# MMC5983MA.net
KiCad netlist of a schematic drawn in Altium Designer
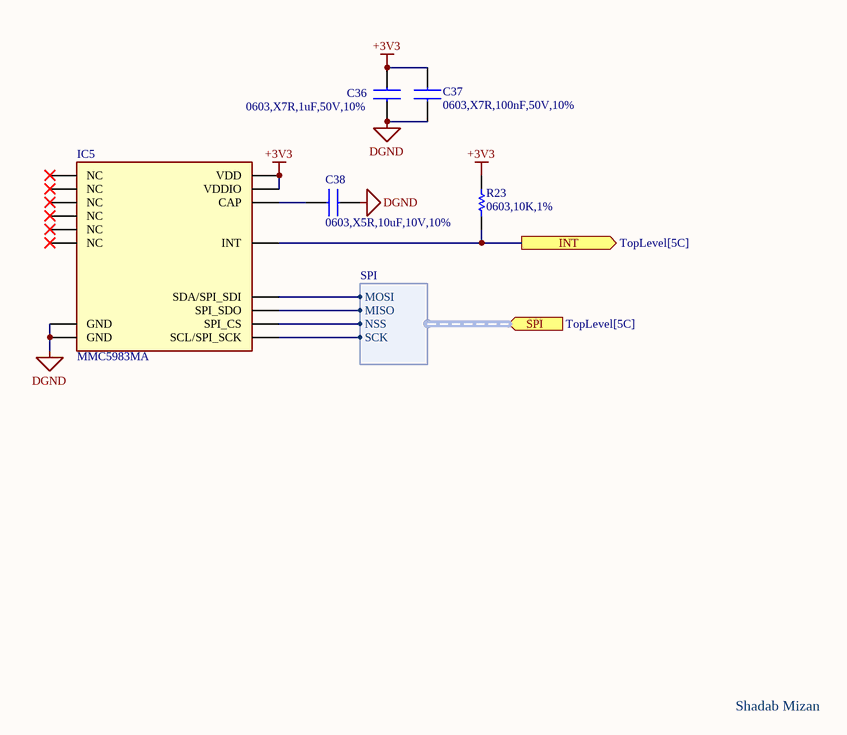
[diagram p0: MMC5983MA.SchDoc]

(export (version "E")
  (design (tool "Eeschema 10.0.6"))
  (components
    (comp (ref "C36")
      (value "0603,X7R,1uF,50V,10%")
      (footprint "CAPC1608X90N")
      (description "50V 1uF X7R ±10% 0603 Multilayer Ceramic Capacitors MLCC - SMD/SMT ROHS")
      (fields (field (name "LCSC PART #") "C15849") (field (name "MANU PART #") "CL10A105KB8NNNC"))
      (libsource (lib "flight-controller") (part "CL10A105KB8NNNC"))
    )
    (comp (ref "C37")
      (value "0603,X7R,100nF,50V,10%")
      (footprint "CAPC1608X90N")
      (description "50V 100nF X7R ±10% 0603 Multilayer Ceramic Capacitors MLCC - SMD/SMT ROHS")
      (fields (field (name "LCSC PART #") "C14663") (field (name "MANU PART #") "CC0603KRX7R9BB104"))
      (libsource (lib "flight-controller") (part "CC0603KRX7R9BB104"))
    )
    (comp (ref "C38")
      (value "0603,X5R,10uF,10V,10%")
      (footprint "CAPC1608X90N")
      (description "10uF ±10% 10V Ceramic Capacitor X5R 0603")
      (fields (field (name "LCSC PART #") "C19702") (field (name "MANU PART #") "CL10A106KP8NNNC"))
      (libsource (lib "flight-controller") (part "CL10A106KP8NNNC"))
    )
    (comp (ref "IC5")
      (value "MMC5983MA")
      (footprint "LGA-16_L3.0-W3.0-P0.50-BL_SQ")
      (description "±8 Gauss, High Performance 3-axis Magnetic Sensor")
      (fields (field (name "LCSC PART #") "C404329"))
      (libsource (lib "flight-controller") (part "MMC5983MA"))
    )
    (comp (ref "R23")
      (value "0603,10K,1%")
      (footprint "RESC1608X90N")
      (description "100mW Thick Film Resistor 75V ±100ppm/℃ ±1% 10kΩ 0603 Chip Resistor - Surface Mount ROHS")
      (fields (field (name "LCSC PART #") "C25804") (field (name "MANU PART #") "0603WAF1002T5E"))
      (libsource (lib "flight-controller") (part "0603WAF1002T5E"))
    )
  )
  (nets
    (net (code "2") (name "+3V3") (class "Default")
      (node (ref "C36") (pin "2") (pinfunction "2_2") (pintype "passive"))
      (node (ref "C37") (pin "2") (pinfunction "2_2") (pintype "passive"))
      (node (ref "IC5") (pin "13") (pinfunction "VDDIO_13") (pintype "passive"))
      (node (ref "IC5") (pin "2") (pinfunction "VDD_2") (pintype "passive"))
      (node (ref "R23") (pin "2") (pinfunction "2_2") (pintype "passive"))
    )
    (net (code "3") (name "/INT") (class "Default")
      (node (ref "IC5") (pin "15") (pinfunction "INT_15") (pintype "passive"))
      (node (ref "R23") (pin "1") (pinfunction "1_1") (pintype "passive"))
    )
    (net (code "4") (name "/MISO") (class "Default")
      (node (ref "IC5") (pin "5") (pinfunction "SPI_SDO_5") (pintype "passive"))
    )
    (net (code "5") (name "/MOSI") (class "Default")
      (node (ref "IC5") (pin "16") (pinfunction "SDA/SPI_SDI_16") (pintype "passive"))
    )
    (net (code "6") (name "/NSS") (class "Default")
      (node (ref "IC5") (pin "4") (pinfunction "SPI_CS_4") (pintype "passive"))
    )
    (net (code "7") (name "/SCK") (class "Default")
      (node (ref "IC5") (pin "1") (pinfunction "SCL/SPI_SCK_1") (pintype "passive"))
    )
    (net (code "9") (name "DGND") (class "Default")
      (node (ref "C36") (pin "1") (pinfunction "1_1") (pintype "passive"))
      (node (ref "C37") (pin "1") (pinfunction "1_1") (pintype "passive"))
      (node (ref "C38") (pin "2") (pinfunction "2_2") (pintype "passive"))
      (node (ref "IC5") (pin "11") (pinfunction "GND_11") (pintype "passive"))
      (node (ref "IC5") (pin "9") (pinfunction "GND_9") (pintype "passive"))
    )
    (net (code "10") (name "Net-(IC5-CAP)") (class "Default")
      (node (ref "C38") (pin "1") (pinfunction "1_1") (pintype "passive"))
      (node (ref "IC5") (pin "10") (pinfunction "CAP_10") (pintype "passive"))
    )
    (net (code "11") (name "unconnected-(IC5-NC-Pad3)") (class "Default")
      (node (ref "IC5") (pin "3") (pinfunction "NC_3") (pintype "passive+no_connect"))
    )
    (net (code "12") (name "unconnected-(IC5-NC-Pad6)") (class "Default")
      (node (ref "IC5") (pin "6") (pinfunction "NC_6") (pintype "passive+no_connect"))
    )
    (net (code "13") (name "unconnected-(IC5-NC-Pad7)") (class "Default")
      (node (ref "IC5") (pin "7") (pinfunction "NC_7") (pintype "passive+no_connect"))
    )
    (net (code "14") (name "unconnected-(IC5-NC-Pad8)") (class "Default")
      (node (ref "IC5") (pin "8") (pinfunction "NC_8") (pintype "passive+no_connect"))
    )
    (net (code "15") (name "unconnected-(IC5-NC-Pad12)") (class "Default")
      (node (ref "IC5") (pin "12") (pinfunction "NC_12") (pintype "passive+no_connect"))
    )
    (net (code "16") (name "unconnected-(IC5-NC-Pad14)") (class "Default")
      (node (ref "IC5") (pin "14") (pinfunction "NC_14") (pintype "passive+no_connect"))
    )
  )
)
